# clock-matrix.net
KiCad netlist of a schematic drawn in EAGLE
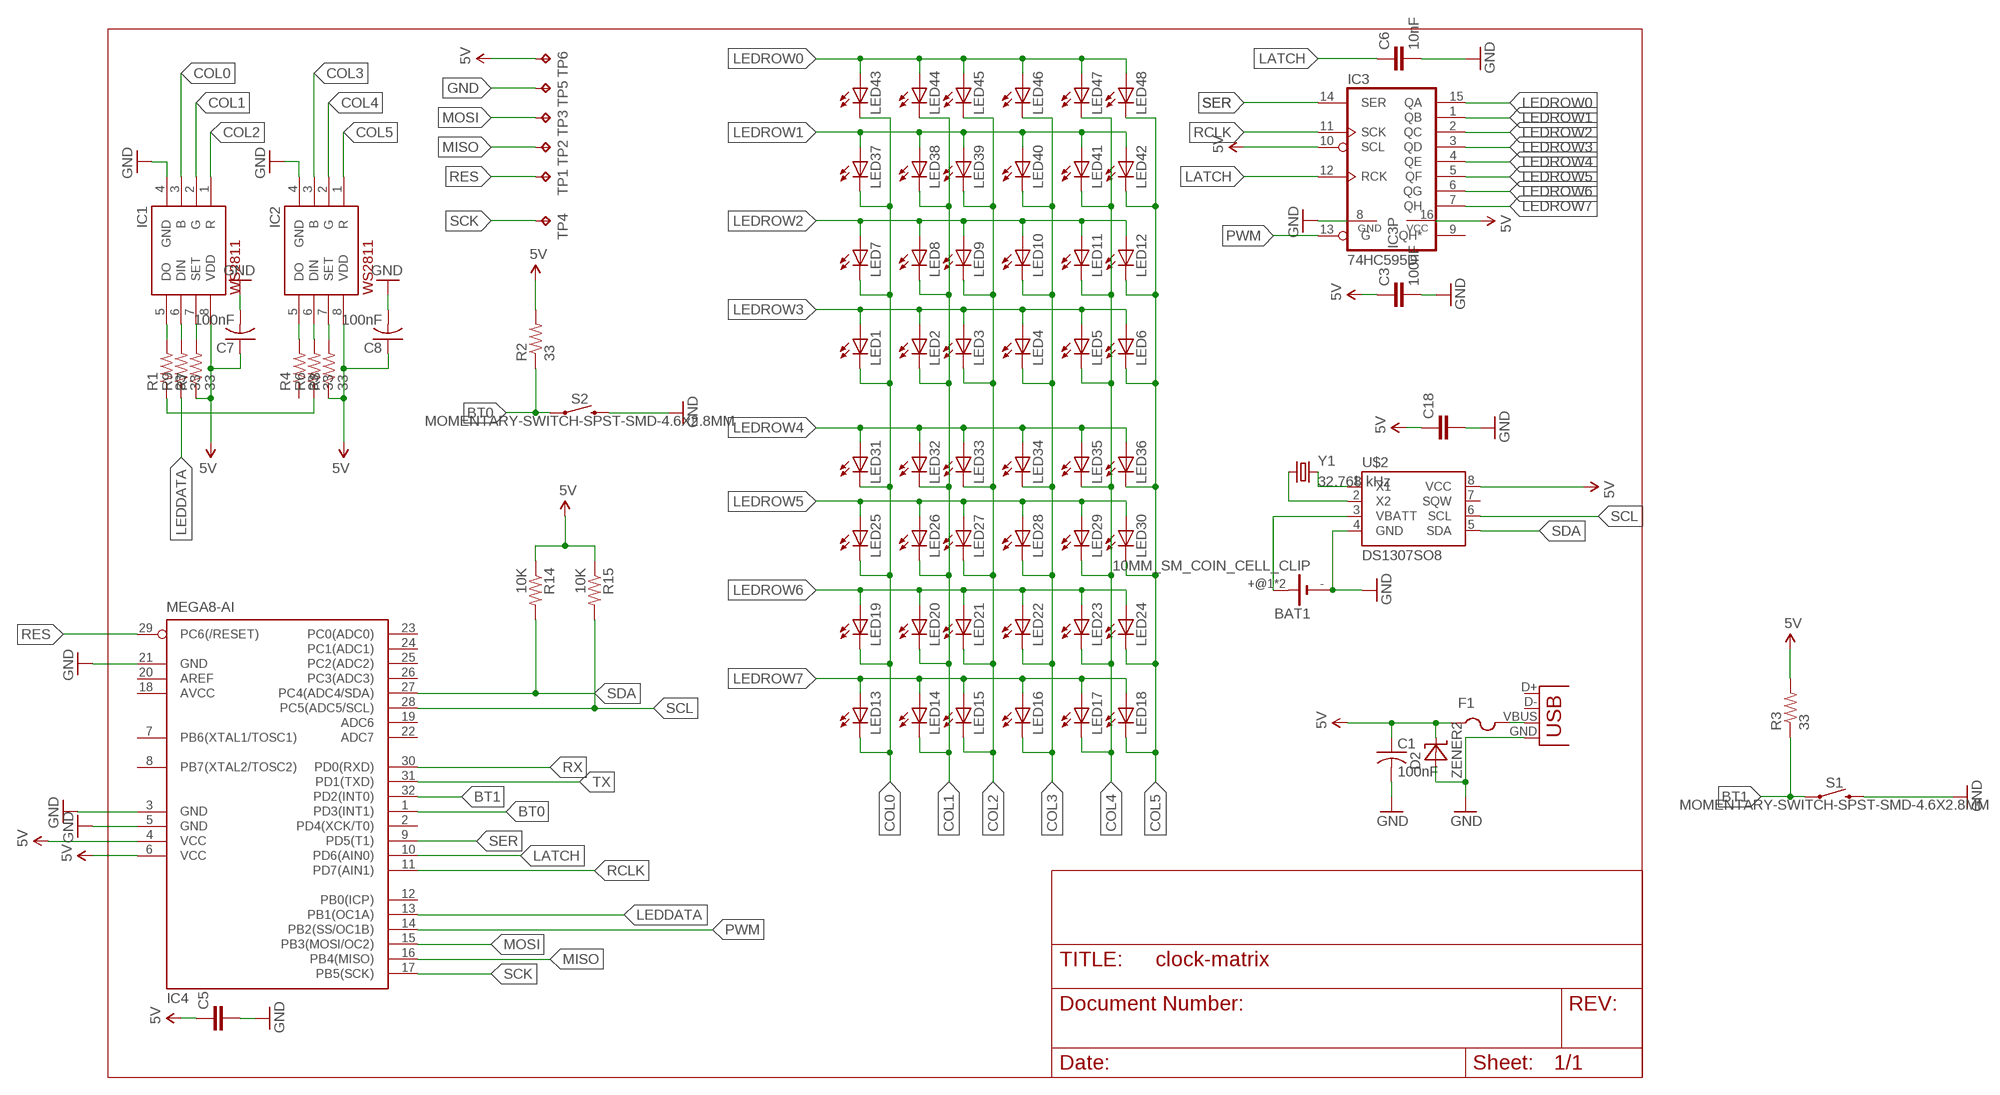
[diagram p0: schematic, sheet 1]

(export (version "E")
  (design (tool "Eeschema 10.0.6"))
  (components
    (comp (ref "BAT1")
      (value "10MM_SM_COIN_CELL_CLIP")
      (footprint "eagle-import:10MM_SM_COIN_CELL_CLIP")
      (libsource (lib "eagle-import") (part "10MM_SM_COIN_CELL_CLIP"))
    )
    (comp (ref "C1")
      (value "100nF")
      (footprint "eagle-import:C0603")
      (libsource (lib "eagle-import") (part "C-USC0603"))
    )
    (comp (ref "C3")
      (value "100nF")
      (footprint "eagle-import:C0603")
      (libsource (lib "eagle-import") (part "C-EUC0603"))
    )
    (comp (ref "C5")
      (value "C-EUC0603")
      (footprint "eagle-import:C0603")
      (libsource (lib "eagle-import") (part "C-EUC0603"))
    )
    (comp (ref "C6")
      (value "10nF")
      (footprint "eagle-import:C0603")
      (libsource (lib "eagle-import") (part "C-EUC0603"))
    )
    (comp (ref "C7")
      (value "100nF")
      (footprint "eagle-import:C0603")
      (libsource (lib "eagle-import") (part "C-USC0603"))
    )
    (comp (ref "C8")
      (value "100nF")
      (footprint "eagle-import:C0603")
      (libsource (lib "eagle-import") (part "C-USC0603"))
    )
    (comp (ref "C18")
      (value "C-EUC0603")
      (footprint "eagle-import:C0603")
      (libsource (lib "eagle-import") (part "C-EUC0603"))
    )
    (comp (ref "D2")
      (value "ZENER2")
      (footprint "eagle-import:SOD123")
      (libsource (lib "eagle-import") (part "ZENER2"))
    )
    (comp (ref "F1")
      (value "PTCFUSE-1206")
      (footprint "eagle-import:R1206")
      (libsource (lib "eagle-import") (part "PTCFUSE-1206"))
    )
    (comp (ref "IC1")
      (value "WS2811-SOP8")
      (footprint "eagle-import:SO08-SKINNYPADS")
      (libsource (lib "eagle-import") (part "WS2811-SOP8"))
    )
    (comp (ref "IC2")
      (value "WS2811-SOP8")
      (footprint "eagle-import:SO08-SKINNYPADS")
      (libsource (lib "eagle-import") (part "WS2811-SOP8"))
    )
    (comp (ref "IC3")
      (value "74HC595D")
      (footprint "eagle-import:SO16")
      (libsource (lib "eagle-import") (part "74595DHC"))
    )
    (comp (ref "IC4")
      (value "MEGA8-AI")
      (footprint "eagle-import:TQFP32-08")
      (fields (field (name "MPN") "ATMEGA8-16AU"))
      (libsource (lib "eagle-import") (part "MEGA8-AI"))
    )
    (comp (ref "LED1")
      (value "LED1206")
      (footprint "eagle-import:LED-1206")
      (libsource (lib "eagle-import") (part "LED1206"))
    )
    (comp (ref "LED2")
      (value "LED1206")
      (footprint "eagle-import:LED-1206")
      (libsource (lib "eagle-import") (part "LED1206"))
    )
    (comp (ref "LED3")
      (value "LED1206")
      (footprint "eagle-import:LED-1206")
      (libsource (lib "eagle-import") (part "LED1206"))
    )
    (comp (ref "LED4")
      (value "LED1206")
      (footprint "eagle-import:LED-1206")
      (libsource (lib "eagle-import") (part "LED1206"))
    )
    (comp (ref "LED5")
      (value "LED1206")
      (footprint "eagle-import:LED-1206")
      (libsource (lib "eagle-import") (part "LED1206"))
    )
    (comp (ref "LED6")
      (value "LED1206")
      (footprint "eagle-import:LED-1206")
      (libsource (lib "eagle-import") (part "LED1206"))
    )
    (comp (ref "LED7")
      (value "LED1206")
      (footprint "eagle-import:LED-1206")
      (libsource (lib "eagle-import") (part "LED1206"))
    )
    (comp (ref "LED8")
      (value "LED1206")
      (footprint "eagle-import:LED-1206")
      (libsource (lib "eagle-import") (part "LED1206"))
    )
    (comp (ref "LED9")
      (value "LED1206")
      (footprint "eagle-import:LED-1206")
      (libsource (lib "eagle-import") (part "LED1206"))
    )
    (comp (ref "LED10")
      (value "LED1206")
      (footprint "eagle-import:LED-1206")
      (libsource (lib "eagle-import") (part "LED1206"))
    )
    (comp (ref "LED11")
      (value "LED1206")
      (footprint "eagle-import:LED-1206")
      (libsource (lib "eagle-import") (part "LED1206"))
    )
    (comp (ref "LED12")
      (value "LED1206")
      (footprint "eagle-import:LED-1206")
      (libsource (lib "eagle-import") (part "LED1206"))
    )
    (comp (ref "LED13")
      (value "LED1206")
      (footprint "eagle-import:LED-1206")
      (libsource (lib "eagle-import") (part "LED1206"))
    )
    (comp (ref "LED14")
      (value "LED1206")
      (footprint "eagle-import:LED-1206")
      (libsource (lib "eagle-import") (part "LED1206"))
    )
    (comp (ref "LED15")
      (value "LED1206")
      (footprint "eagle-import:LED-1206")
      (libsource (lib "eagle-import") (part "LED1206"))
    )
    (comp (ref "LED16")
      (value "LED1206")
      (footprint "eagle-import:LED-1206")
      (libsource (lib "eagle-import") (part "LED1206"))
    )
    (comp (ref "LED17")
      (value "LED1206")
      (footprint "eagle-import:LED-1206")
      (libsource (lib "eagle-import") (part "LED1206"))
    )
    (comp (ref "LED18")
      (value "LED1206")
      (footprint "eagle-import:LED-1206")
      (libsource (lib "eagle-import") (part "LED1206"))
    )
    (comp (ref "LED19")
      (value "LED1206")
      (footprint "eagle-import:LED-1206")
      (libsource (lib "eagle-import") (part "LED1206"))
    )
    (comp (ref "LED20")
      (value "LED1206")
      (footprint "eagle-import:LED-1206")
      (libsource (lib "eagle-import") (part "LED1206"))
    )
    (comp (ref "LED21")
      (value "LED1206")
      (footprint "eagle-import:LED-1206")
      (libsource (lib "eagle-import") (part "LED1206"))
    )
    (comp (ref "LED22")
      (value "LED1206")
      (footprint "eagle-import:LED-1206")
      (libsource (lib "eagle-import") (part "LED1206"))
    )
    (comp (ref "LED23")
      (value "LED1206")
      (footprint "eagle-import:LED-1206")
      (libsource (lib "eagle-import") (part "LED1206"))
    )
    (comp (ref "LED24")
      (value "LED1206")
      (footprint "eagle-import:LED-1206")
      (libsource (lib "eagle-import") (part "LED1206"))
    )
    (comp (ref "LED25")
      (value "LED1206")
      (footprint "eagle-import:LED-1206")
      (libsource (lib "eagle-import") (part "LED1206"))
    )
    (comp (ref "LED26")
      (value "LED1206")
      (footprint "eagle-import:LED-1206")
      (libsource (lib "eagle-import") (part "LED1206"))
    )
    (comp (ref "LED27")
      (value "LED1206")
      (footprint "eagle-import:LED-1206")
      (libsource (lib "eagle-import") (part "LED1206"))
    )
    (comp (ref "LED28")
      (value "LED1206")
      (footprint "eagle-import:LED-1206")
      (libsource (lib "eagle-import") (part "LED1206"))
    )
    (comp (ref "LED29")
      (value "LED1206")
      (footprint "eagle-import:LED-1206")
      (libsource (lib "eagle-import") (part "LED1206"))
    )
    (comp (ref "LED30")
      (value "LED1206")
      (footprint "eagle-import:LED-1206")
      (libsource (lib "eagle-import") (part "LED1206"))
    )
    (comp (ref "LED31")
      (value "LED1206")
      (footprint "eagle-import:LED-1206")
      (libsource (lib "eagle-import") (part "LED1206"))
    )
    (comp (ref "LED32")
      (value "LED1206")
      (footprint "eagle-import:LED-1206")
      (libsource (lib "eagle-import") (part "LED1206"))
    )
    (comp (ref "LED33")
      (value "LED1206")
      (footprint "eagle-import:LED-1206")
      (libsource (lib "eagle-import") (part "LED1206"))
    )
    (comp (ref "LED34")
      (value "LED1206")
      (footprint "eagle-import:LED-1206")
      (libsource (lib "eagle-import") (part "LED1206"))
    )
    (comp (ref "LED35")
      (value "LED1206")
      (footprint "eagle-import:LED-1206")
      (libsource (lib "eagle-import") (part "LED1206"))
    )
    (comp (ref "LED36")
      (value "LED1206")
      (footprint "eagle-import:LED-1206")
      (libsource (lib "eagle-import") (part "LED1206"))
    )
    (comp (ref "LED37")
      (value "LED1206")
      (footprint "eagle-import:LED-1206")
      (libsource (lib "eagle-import") (part "LED1206"))
    )
    (comp (ref "LED38")
      (value "LED1206")
      (footprint "eagle-import:LED-1206")
      (libsource (lib "eagle-import") (part "LED1206"))
    )
    (comp (ref "LED39")
      (value "LED1206")
      (footprint "eagle-import:LED-1206")
      (libsource (lib "eagle-import") (part "LED1206"))
    )
    (comp (ref "LED40")
      (value "LED1206")
      (footprint "eagle-import:LED-1206")
      (libsource (lib "eagle-import") (part "LED1206"))
    )
    (comp (ref "LED41")
      (value "LED1206")
      (footprint "eagle-import:LED-1206")
      (libsource (lib "eagle-import") (part "LED1206"))
    )
    (comp (ref "LED42")
      (value "LED1206")
      (footprint "eagle-import:LED-1206")
      (libsource (lib "eagle-import") (part "LED1206"))
    )
    (comp (ref "LED43")
      (value "LED1206")
      (footprint "eagle-import:LED-1206")
      (libsource (lib "eagle-import") (part "LED1206"))
    )
    (comp (ref "LED44")
      (value "LED1206")
      (footprint "eagle-import:LED-1206")
      (libsource (lib "eagle-import") (part "LED1206"))
    )
    (comp (ref "LED45")
      (value "LED1206")
      (footprint "eagle-import:LED-1206")
      (libsource (lib "eagle-import") (part "LED1206"))
    )
    (comp (ref "LED46")
      (value "LED1206")
      (footprint "eagle-import:LED-1206")
      (libsource (lib "eagle-import") (part "LED1206"))
    )
    (comp (ref "LED47")
      (value "LED1206")
      (footprint "eagle-import:LED-1206")
      (libsource (lib "eagle-import") (part "LED1206"))
    )
    (comp (ref "LED48")
      (value "LED1206")
      (footprint "eagle-import:LED-1206")
      (libsource (lib "eagle-import") (part "LED1206"))
    )
    (comp (ref "R1")
      (value "33")
      (footprint "eagle-import:R0603")
      (libsource (lib "eagle-import") (part "R-US_R0603"))
    )
    (comp (ref "R2")
      (value "33")
      (footprint "eagle-import:R0603")
      (libsource (lib "eagle-import") (part "R-US_R0603"))
    )
    (comp (ref "R3")
      (value "33")
      (footprint "eagle-import:R0603")
      (libsource (lib "eagle-import") (part "R-US_R0603"))
    )
    (comp (ref "R4")
      (value "33")
      (footprint "eagle-import:R0603")
      (libsource (lib "eagle-import") (part "R-US_R0603"))
    )
    (comp (ref "R6")
      (value "33")
      (footprint "eagle-import:R0603")
      (libsource (lib "eagle-import") (part "R-US_R0603"))
    )
    (comp (ref "R7")
      (value "33")
      (footprint "eagle-import:R0603")
      (libsource (lib "eagle-import") (part "R-US_R0603"))
    )
    (comp (ref "R8")
      (value "33")
      (footprint "eagle-import:R0603")
      (libsource (lib "eagle-import") (part "R-US_R0603"))
    )
    (comp (ref "R9")
      (value "33")
      (footprint "eagle-import:R0603")
      (libsource (lib "eagle-import") (part "R-US_R0603"))
    )
    (comp (ref "R14")
      (value "10K")
      (footprint "eagle-import:R0603")
      (libsource (lib "eagle-import") (part "rcl_R-US_R0603"))
    )
    (comp (ref "R15")
      (value "10K")
      (footprint "eagle-import:R0603")
      (libsource (lib "eagle-import") (part "rcl_R-US_R0603"))
    )
    (comp (ref "S1")
      (value "MOMENTARY-SWITCH-SPST-SMD-4.6X2.8MM")
      (footprint "eagle-import:TACTILE_SWITCH_SMD_4.6X2.8MM")
      (libsource (lib "eagle-import") (part "MOMENTARY-SWITCH-SPST-SMD-4.6X2.8MM"))
    )
    (comp (ref "S2")
      (value "MOMENTARY-SWITCH-SPST-SMD-4.6X2.8MM")
      (footprint "eagle-import:TACTILE_SWITCH_SMD_4.6X2.8MM")
      (libsource (lib "eagle-import") (part "MOMENTARY-SWITCH-SPST-SMD-4.6X2.8MM"))
    )
    (comp (ref "TP1")
      (value "TPTP10R")
      (footprint "eagle-import:TP10R")
      (libsource (lib "eagle-import") (part "TPTP10R"))
    )
    (comp (ref "TP2")
      (value "TPTP10R")
      (footprint "eagle-import:TP10R")
      (libsource (lib "eagle-import") (part "TPTP10R"))
    )
    (comp (ref "TP3")
      (value "TPTP10R")
      (footprint "eagle-import:TP10R")
      (libsource (lib "eagle-import") (part "TPTP10R"))
    )
    (comp (ref "TP4")
      (value "TPTP10R")
      (footprint "eagle-import:TP10R")
      (libsource (lib "eagle-import") (part "TPTP10R"))
    )
    (comp (ref "TP5")
      (value "TPTP10R")
      (footprint "eagle-import:TP10R")
      (libsource (lib "eagle-import") (part "TPTP10R"))
    )
    (comp (ref "TP6")
      (value "TPTP10R")
      (footprint "eagle-import:TP10R")
      (libsource (lib "eagle-import") (part "TPTP10R"))
    )
    (comp (ref "U$2")
      (value "DS1307SO8")
      (footprint "eagle-import:SO08")
      (libsource (lib "eagle-import") (part "DS1307SO8"))
    )
    (comp (ref "X2")
      (value "USB-MICROB")
      (footprint "eagle-import:USB-MICROB")
      (libsource (lib "eagle-import") (part "USB-MICROB"))
    )
    (comp (ref "Y1")
      (value "32.768 kHz")
      (footprint "eagle-import:TC26H")
      (libsource (lib "eagle-import") (part "CRYSTALTC26H"))
    )
  )
  (nets
    (net (code "1") (name "/AVCC") (class "Default")
      (node (ref "IC4") (pin "18") (pinfunction "AVCC_18") (pintype "power_in"))
    )
    (net (code "2") (name "5V") (class "Default")
      (node (ref "C1") (pin "1") (pinfunction "1_1") (pintype "passive"))
      (node (ref "C18") (pin "1") (pinfunction "1_1") (pintype "passive"))
      (node (ref "C3") (pin "1") (pinfunction "1_1") (pintype "passive"))
      (node (ref "C5") (pin "1") (pinfunction "1_1") (pintype "passive"))
      (node (ref "C7") (pin "1") (pinfunction "1_1") (pintype "passive"))
      (node (ref "C8") (pin "1") (pinfunction "1_1") (pintype "passive"))
      (node (ref "D2") (pin "C") (pinfunction "C_C") (pintype "passive"))
      (node (ref "F1") (pin "1") (pinfunction "1_1") (pintype "passive"))
      (node (ref "IC1") (pin "8") (pinfunction "VDD_8") (pintype "power_in"))
      (node (ref "IC2") (pin "8") (pinfunction "VDD_8") (pintype "power_in"))
      (node (ref "IC3") (pin "10") (pinfunction "SCL_10") (pintype "input"))
      (node (ref "IC3") (pin "16") (pinfunction "VCC_16") (pintype "power_in"))
      (node (ref "IC4") (pin "4") (pinfunction "VCC_4") (pintype "power_in"))
      (node (ref "IC4") (pin "6") (pinfunction "VCC_6") (pintype "power_in"))
      (node (ref "R14") (pin "1") (pinfunction "1_1") (pintype "passive"))
      (node (ref "R15") (pin "1") (pinfunction "1_1") (pintype "passive"))
      (node (ref "R2") (pin "2") (pinfunction "2_2") (pintype "passive"))
      (node (ref "R3") (pin "2") (pinfunction "2_2") (pintype "passive"))
      (node (ref "R7") (pin "1") (pinfunction "1_1") (pintype "passive"))
      (node (ref "R8") (pin "1") (pinfunction "1_1") (pintype "passive"))
      (node (ref "TP6") (pin "TP") (pinfunction "TP_TP") (pintype "input"))
      (node (ref "U$2") (pin "8") (pinfunction "VCC_8") (pintype "bidirectional"))
    )
    (net (code "3") (name "BT0") (class "Default")
      (node (ref "IC4") (pin "1") (pinfunction "PD3(INT1)_1") (pintype "bidirectional"))
      (node (ref "R2") (pin "1") (pinfunction "1_1") (pintype "passive"))
      (node (ref "S2") (pin "1") (pinfunction "1_1") (pintype "passive"))
      (node (ref "S2") (pin "2") (pinfunction "1_2") (pintype "passive"))
    )
    (net (code "4") (name "BT1") (class "Default")
      (node (ref "IC4") (pin "32") (pinfunction "PD2(INT0)_32") (pintype "bidirectional"))
      (node (ref "R3") (pin "1") (pinfunction "1_1") (pintype "passive"))
      (node (ref "S1") (pin "1") (pinfunction "1_1") (pintype "passive"))
      (node (ref "S1") (pin "2") (pinfunction "1_2") (pintype "passive"))
    )
    (net (code "5") (name "COL0") (class "Default")
      (node (ref "IC1") (pin "3") (pinfunction "B_3") (pintype "open_collector"))
      (node (ref "LED1") (pin "C") (pinfunction "C_C") (pintype "passive"))
      (node (ref "LED13") (pin "C") (pinfunction "C_C") (pintype "passive"))
      (node (ref "LED19") (pin "C") (pinfunction "C_C") (pintype "passive"))
      (node (ref "LED25") (pin "C") (pinfunction "C_C") (pintype "passive"))
      (node (ref "LED31") (pin "C") (pinfunction "C_C") (pintype "passive"))
      (node (ref "LED37") (pin "C") (pinfunction "C_C") (pintype "passive"))
      (node (ref "LED43") (pin "C") (pinfunction "C_C") (pintype "passive"))
      (node (ref "LED7") (pin "C") (pinfunction "C_C") (pintype "passive"))
    )
    (net (code "6") (name "COL1") (class "Default")
      (node (ref "IC1") (pin "2") (pinfunction "G_2") (pintype "open_collector"))
      (node (ref "LED14") (pin "C") (pinfunction "C_C") (pintype "passive"))
      (node (ref "LED2") (pin "C") (pinfunction "C_C") (pintype "passive"))
      (node (ref "LED20") (pin "C") (pinfunction "C_C") (pintype "passive"))
      (node (ref "LED26") (pin "C") (pinfunction "C_C") (pintype "passive"))
      (node (ref "LED32") (pin "C") (pinfunction "C_C") (pintype "passive"))
      (node (ref "LED38") (pin "C") (pinfunction "C_C") (pintype "passive"))
      (node (ref "LED44") (pin "C") (pinfunction "C_C") (pintype "passive"))
      (node (ref "LED8") (pin "C") (pinfunction "C_C") (pintype "passive"))
    )
    (net (code "7") (name "COL2") (class "Default")
      (node (ref "IC1") (pin "1") (pinfunction "R_1") (pintype "open_collector"))
      (node (ref "LED15") (pin "C") (pinfunction "C_C") (pintype "passive"))
      (node (ref "LED21") (pin "C") (pinfunction "C_C") (pintype "passive"))
      (node (ref "LED27") (pin "C") (pinfunction "C_C") (pintype "passive"))
      (node (ref "LED3") (pin "C") (pinfunction "C_C") (pintype "passive"))
      (node (ref "LED33") (pin "C") (pinfunction "C_C") (pintype "passive"))
      (node (ref "LED39") (pin "C") (pinfunction "C_C") (pintype "passive"))
      (node (ref "LED45") (pin "C") (pinfunction "C_C") (pintype "passive"))
      (node (ref "LED9") (pin "C") (pinfunction "C_C") (pintype "passive"))
    )
    (net (code "8") (name "COL3") (class "Default")
      (node (ref "IC2") (pin "3") (pinfunction "B_3") (pintype "open_collector"))
      (node (ref "LED10") (pin "C") (pinfunction "C_C") (pintype "passive"))
      (node (ref "LED16") (pin "C") (pinfunction "C_C") (pintype "passive"))
      (node (ref "LED22") (pin "C") (pinfunction "C_C") (pintype "passive"))
      (node (ref "LED28") (pin "C") (pinfunction "C_C") (pintype "passive"))
      (node (ref "LED34") (pin "C") (pinfunction "C_C") (pintype "passive"))
      (node (ref "LED4") (pin "C") (pinfunction "C_C") (pintype "passive"))
      (node (ref "LED40") (pin "C") (pinfunction "C_C") (pintype "passive"))
      (node (ref "LED46") (pin "C") (pinfunction "C_C") (pintype "passive"))
    )
    (net (code "9") (name "COL4") (class "Default")
      (node (ref "IC2") (pin "2") (pinfunction "G_2") (pintype "open_collector"))
      (node (ref "LED11") (pin "C") (pinfunction "C_C") (pintype "passive"))
      (node (ref "LED17") (pin "C") (pinfunction "C_C") (pintype "passive"))
      (node (ref "LED23") (pin "C") (pinfunction "C_C") (pintype "passive"))
      (node (ref "LED29") (pin "C") (pinfunction "C_C") (pintype "passive"))
      (node (ref "LED35") (pin "C") (pinfunction "C_C") (pintype "passive"))
      (node (ref "LED41") (pin "C") (pinfunction "C_C") (pintype "passive"))
      (node (ref "LED47") (pin "C") (pinfunction "C_C") (pintype "passive"))
      (node (ref "LED5") (pin "C") (pinfunction "C_C") (pintype "passive"))
    )
    (net (code "10") (name "COL5") (class "Default")
      (node (ref "IC2") (pin "1") (pinfunction "R_1") (pintype "open_collector"))
      (node (ref "LED12") (pin "C") (pinfunction "C_C") (pintype "passive"))
      (node (ref "LED18") (pin "C") (pinfunction "C_C") (pintype "passive"))
      (node (ref "LED24") (pin "C") (pinfunction "C_C") (pintype "passive"))
      (node (ref "LED30") (pin "C") (pinfunction "C_C") (pintype "passive"))
      (node (ref "LED36") (pin "C") (pinfunction "C_C") (pintype "passive"))
      (node (ref "LED42") (pin "C") (pinfunction "C_C") (pintype "passive"))
      (node (ref "LED48") (pin "C") (pinfunction "C_C") (pintype "passive"))
      (node (ref "LED6") (pin "C") (pinfunction "C_C") (pintype "passive"))
    )
    (net (code "11") (name "GND") (class "Default")
      (node (ref "BAT1") (pin "-") (pinfunction "-_-") (pintype "passive"))
      (node (ref "C1") (pin "2") (pinfunction "2_2") (pintype "passive"))
      (node (ref "C18") (pin "2") (pinfunction "2_2") (pintype "passive"))
      (node (ref "C3") (pin "2") (pinfunction "2_2") (pintype "passive"))
      (node (ref "C5") (pin "2") (pinfunction "2_2") (pintype "passive"))
      (node (ref "C6") (pin "2") (pinfunction "2_2") (pintype "passive"))
      (node (ref "C7") (pin "2") (pinfunction "2_2") (pintype "passive"))
      (node (ref "C8") (pin "2") (pinfunction "2_2") (pintype "passive"))
      (node (ref "D2") (pin "A") (pinfunction "A_A") (pintype "passive"))
      (node (ref "IC1") (pin "4") (pinfunction "GND_4") (pintype "power_in"))
      (node (ref "IC2") (pin "4") (pinfunction "GND_4") (pintype "power_in"))
      (node (ref "IC3") (pin "8") (pinfunction "GND_8") (pintype "power_in"))
      (node (ref "IC4") (pin "21") (pinfunction "GND_21") (pintype "power_in"))
      (node (ref "IC4") (pin "3") (pinfunction "GND_3") (pintype "power_in"))
      (node (ref "IC4") (pin "5") (pinfunction "GND_5") (pintype "power_in"))
      (node (ref "S1") (pin "3") (pinfunction "2_3") (pintype "passive"))
      (node (ref "S1") (pin "4") (pinfunction "2_4") (pintype "passive"))
      (node (ref "S2") (pin "3") (pinfunction "2_3") (pintype "passive"))
      (node (ref "S2") (pin "4") (pinfunction "2_4") (pintype "passive"))
      (node (ref "TP5") (pin "TP") (pinfunction "TP_TP") (pintype "input"))
      (node (ref "U$2") (pin "4") (pinfunction "GND_4") (pintype "bidirectional"))
      (node (ref "X2") (pin "GND") (pinfunction "GND_GND") (pintype "bidirectional"))
    )
    (net (code "12") (name "LATCH") (class "Default")
      (node (ref "C6") (pin "1") (pinfunction "1_1") (pintype "passive"))
      (node (ref "IC3") (pin "12") (pinfunction "RCK_12") (pintype "input"))
      (node (ref "IC4") (pin "10") (pinfunction "PD6(AIN0)_10") (pintype "bidirectional"))
    )
    (net (code "13") (name "LEDDATA") (class "Default")
      (node (ref "IC4") (pin "13") (pinfunction "PB1(OC1A)_13") (pintype "bidirectional"))
      (node (ref "R9") (pin "1") (pinfunction "1_1") (pintype "passive"))
    )
    (net (code "14") (name "LEDROW0") (class "Default")
      (node (ref "IC3") (pin "15") (pinfunction "QA_15") (pintype "tri_state"))
      (node (ref "LED43") (pin "A") (pinfunction "A_A") (pintype "passive"))
      (node (ref "LED44") (pin "A") (pinfunction "A_A") (pintype "passive"))
      (node (ref "LED45") (pin "A") (pinfunction "A_A") (pintype "passive"))
      (node (ref "LED46") (pin "A") (pinfunction "A_A") (pintype "passive"))
      (node (ref "LED47") (pin "A") (pinfunction "A_A") (pintype "passive"))
      (node (ref "LED48") (pin "A") (pinfunction "A_A") (pintype "passive"))
    )
    (net (code "15") (name "LEDROW1") (class "Default")
      (node (ref "IC3") (pin "1") (pinfunction "QB_1") (pintype "tri_state"))
      (node (ref "LED37") (pin "A") (pinfunction "A_A") (pintype "passive"))
      (node (ref "LED38") (pin "A") (pinfunction "A_A") (pintype "passive"))
      (node (ref "LED39") (pin "A") (pinfunction "A_A") (pintype "passive"))
      (node (ref "LED40") (pin "A") (pinfunction "A_A") (pintype "passive"))
      (node (ref "LED41") (pin "A") (pinfunction "A_A") (pintype "passive"))
      (node (ref "LED42") (pin "A") (pinfunction "A_A") (pintype "passive"))
    )
    (net (code "16") (name "LEDROW2") (class "Default")
      (node (ref "IC3") (pin "2") (pinfunction "QC_2") (pintype "tri_state"))
      (node (ref "LED10") (pin "A") (pinfunction "A_A") (pintype "passive"))
      (node (ref "LED11") (pin "A") (pinfunction "A_A") (pintype "passive"))
      (node (ref "LED12") (pin "A") (pinfunction "A_A") (pintype "passive"))
      (node (ref "LED7") (pin "A") (pinfunction "A_A") (pintype "passive"))
      (node (ref "LED8") (pin "A") (pinfunction "A_A") (pintype "passive"))
      (node (ref "LED9") (pin "A") (pinfunction "A_A") (pintype "passive"))
    )
    (net (code "17") (name "LEDROW3") (class "Default")
      (node (ref "IC3") (pin "3") (pinfunction "QD_3") (pintype "tri_state"))
      (node (ref "LED1") (pin "A") (pinfunction "A_A") (pintype "passive"))
      (node (ref "LED2") (pin "A") (pinfunction "A_A") (pintype "passive"))
      (node (ref "LED3") (pin "A") (pinfunction "A_A") (pintype "passive"))
      (node (ref "LED4") (pin "A") (pinfunction "A_A") (pintype "passive"))
      (node (ref "LED5") (pin "A") (pinfunction "A_A") (pintype "passive"))
      (node (ref "LED6") (pin "A") (pinfunction "A_A") (pintype "passive"))
    )
    (net (code "18") (name "LEDROW4") (class "Default")
      (node (ref "IC3") (pin "4") (pinfunction "QE_4") (pintype "tri_state"))
      (node (ref "LED31") (pin "A") (pinfunction "A_A") (pintype "passive"))
      (node (ref "LED32") (pin "A") (pinfunction "A_A") (pintype "passive"))
      (node (ref "LED33") (pin "A") (pinfunction "A_A") (pintype "passive"))
      (node (ref "LED34") (pin "A") (pinfunction "A_A") (pintype "passive"))
      (node (ref "LED35") (pin "A") (pinfunction "A_A") (pintype "passive"))
      (node (ref "LED36") (pin "A") (pinfunction "A_A") (pintype "passive"))
    )
    (net (code "19") (name "LEDROW5") (class "Default")
      (node (ref "IC3") (pin "5") (pinfunction "QF_5") (pintype "tri_state"))
      (node (ref "LED25") (pin "A") (pinfunction "A_A") (pintype "passive"))
      (node (ref "LED26") (pin "A") (pinfunction "A_A") (pintype "passive"))
      (node (ref "LED27") (pin "A") (pinfunction "A_A") (pintype "passive"))
      (node (ref "LED28") (pin "A") (pinfunction "A_A") (pintype "passive"))
      (node (ref "LED29") (pin "A") (pinfunction "A_A") (pintype "passive"))
      (node (ref "LED30") (pin "A") (pinfunction "A_A") (pintype "passive"))
    )
    (net (code "20") (name "LEDROW6") (class "Default")
      (node (ref "IC3") (pin "6") (pinfunction "QG_6") (pintype "tri_state"))
      (node (ref "LED19") (pin "A") (pinfunction "A_A") (pintype "passive"))
      (node (ref "LED20") (pin "A") (pinfunction "A_A") (pintype "passive"))
      (node (ref "LED21") (pin "A") (pinfunction "A_A") (pintype "passive"))
      (node (ref "LED22") (pin "A") (pinfunction "A_A") (pintype "passive"))
      (node (ref "LED23") (pin "A") (pinfunction "A_A") (pintype "passive"))
      (node (ref "LED24") (pin "A") (pinfunction "A_A") (pintype "passive"))
    )
    (net (code "21") (name "LEDROW7") (class "Default")
      (node (ref "IC3") (pin "7") (pinfunction "QH_7") (pintype "tri_state"))
      (node (ref "LED13") (pin "A") (pinfunction "A_A") (pintype "passive"))
      (node (ref "LED14") (pin "A") (pinfunction "A_A") (pintype "passive"))
      (node (ref "LED15") (pin "A") (pinfunction "A_A") (pintype "passive"))
      (node (ref "LED16") (pin "A") (pinfunction "A_A") (pintype "passive"))
      (node (ref "LED17") (pin "A") (pinfunction "A_A") (pintype "passive"))
      (node (ref "LED18") (pin "A") (pinfunction "A_A") (pintype "passive"))
    )
    (net (code "22") (name "MISO") (class "Default")
      (node (ref "IC4") (pin "16") (pinfunction "PB4(MISO)_16") (pintype "bidirectional"))
      (node (ref "TP2") (pin "TP") (pinfunction "TP_TP") (pintype "input"))
    )
    (net (code "23") (name "MOSI") (class "Default")
      (node (ref "IC4") (pin "15") (pinfunction "PB3(MOSI/OC2)_15") (pintype "bidirectional"))
      (node (ref "TP3") (pin "TP") (pinfunction "TP_TP") (pintype "input"))
    )
    (net (code "24") (name "Net-(F1-Pad2)") (class "Default")
      (node (ref "F1") (pin "2") (pinfunction "2_2") (pintype "passive"))
      (node (ref "X2") (pin "VBUS") (pinfunction "VBUS_VBUS") (pintype "bidirectional"))
    )
    (net (code "25") (name "Net-(IC1-DIN)") (class "Default")
      (node (ref "IC1") (pin "6") (pinfunction "DIN_6") (pintype "input"))
      (node (ref "R9") (pin "2") (pinfunction "2_2") (pintype "passive"))
    )
    (net (code "26") (name "Net-(IC1-DO)") (class "Default")
      (node (ref "IC1") (pin "5") (pinfunction "DO_5") (pintype "output"))
      (node (ref "R1") (pin "2") (pinfunction "2_2") (pintype "passive"))
    )
    (net (code "27") (name "Net-(IC1-SET)") (class "Default")
      (node (ref "IC1") (pin "7") (pinfunction "SET_7") (pintype "input"))
      (node (ref "R7") (pin "2") (pinfunction "2_2") (pintype "passive"))
    )
    (net (code "28") (name "Net-(IC2-DIN)") (class "Default")
      (node (ref "IC2") (pin "6") (pinfunction "DIN_6") (pintype "input"))
      (node (ref "R6") (pin "2") (pinfunction "2_2") (pintype "passive"))
    )
    (net (code "29") (name "Net-(IC2-DO)") (class "Default")
      (node (ref "IC2") (pin "5") (pinfunction "DO_5") (pintype "output"))
      (node (ref "R4") (pin "2") (pinfunction "2_2") (pintype "passive"))
    )
    (net (code "30") (name "Net-(IC2-SET)") (class "Default")
      (node (ref "IC2") (pin "7") (pinfunction "SET_7") (pintype "input"))
      (node (ref "R8") (pin "2") (pinfunction "2_2") (pintype "passive"))
    )
    (net (code "31") (name "Net-(R1-Pad1)") (class "Default")
      (node (ref "R1") (pin "1") (pinfunction "1_1") (pintype "passive"))
      (node (ref "R6") (pin "1") (pinfunction "1_1") (pintype "passive"))
    )
    (net (code "32") (name "Net-(U$2-VBATT)") (class "Default")
      (node (ref "BAT1") (pin "+@1") (pinfunction "+_+@1") (pintype "passive"))
      (node (ref "BAT1") (pin "+@2") (pinfunction "+_+@2") (pintype "passive"))
      (node (ref "U$2") (pin "3") (pinfunction "VBATT_3") (pintype "bidirectional"))
    )
    (net (code "33") (name "Net-(U$2-X1)") (class "Default")
      (node (ref "U$2") (pin "1") (pinfunction "X1_1") (pintype "bidirectional"))
      (node (ref "Y1") (pin "2") (pinfunction "2_2") (pintype "passive"))
    )
    (net (code "34") (name "Net-(U$2-X2)") (class "Default")
      (node (ref "U$2") (pin "2") (pinfunction "X2_2") (pintype "bidirectional"))
      (node (ref "Y1") (pin "1") (pinfunction "1_1") (pintype "passive"))
    )
    (net (code "35") (name "PWM") (class "Default")
      (node (ref "IC3") (pin "13") (pinfunction "G_13") (pintype "input"))
      (node (ref "IC4") (pin "14") (pinfunction "PB2(SS/OC1B)_14") (pintype "bidirectional"))
    )
    (net (code "36") (name "RCLK") (class "Default")
      (node (ref "IC3") (pin "11") (pinfunction "SCK_11") (pintype "input"))
      (node (ref "IC4") (pin "11") (pinfunction "PD7(AIN1)_11") (pintype "bidirectional"))
    )
    (net (code "37") (name "RES") (class "Default")
      (node (ref "IC4") (pin "29") (pinfunction "PC6(/RESET)_29") (pintype "bidirectional"))
      (node (ref "TP1") (pin "TP") (pinfunction "TP_TP") (pintype "input"))
    )
    (net (code "38") (name "RX") (class "Default")
      (node (ref "IC4") (pin "30") (pinfunction "PD0(RXD)_30") (pintype "bidirectional"))
    )
    (net (code "39") (name "SCK") (class "Default")
      (node (ref "IC4") (pin "17") (pinfunction "PB5(SCK)_17") (pintype "bidirectional"))
      (node (ref "TP4") (pin "TP") (pinfunction "TP_TP") (pintype "input"))
    )
    (net (code "40") (name "SCL") (class "Default")
      (node (ref "IC4") (pin "28") (pinfunction "PC5(ADC5/SCL)_28") (pintype "bidirectional"))
      (node (ref "R15") (pin "2") (pinfunction "2_2") (pintype "passive"))
      (node (ref "U$2") (pin "6") (pinfunction "SCL_6") (pintype "bidirectional"))
    )
    (net (code "41") (name "SDA") (class "Default")
      (node (ref "IC4") (pin "27") (pinfunction "PC4(ADC4/SDA)_27") (pintype "bidirectional"))
      (node (ref "R14") (pin "2") (pinfunction "2_2") (pintype "passive"))
      (node (ref "U$2") (pin "5") (pinfunction "SDA_5") (pintype "bidirectional"))
    )
    (net (code "42") (name "SER") (class "Default")
      (node (ref "IC3") (pin "14") (pinfunction "SER_14") (pintype "input"))
      (node (ref "IC4") (pin "9") (pinfunction "PD5(T1)_9") (pintype "bidirectional"))
    )
    (net (code "43") (name "TX") (class "Default")
      (node (ref "IC4") (pin "31") (pinfunction "PD1(TXD)_31") (pintype "bidirectional"))
    )
    (net (code "44") (name "unconnected-(IC3A-QH*-Pad9)") (class "Default")
      (node (ref "IC3") (pin "9") (pinfunction "QH*_9") (pintype "tri_state"))
    )
    (net (code "45") (name "unconnected-(IC4-ADC6-Pad19)") (class "Default")
      (node (ref "IC4") (pin "19") (pinfunction "ADC6_19") (pintype "bidirectional"))
    )
    (net (code "46") (name "unconnected-(IC4-ADC7-Pad22)") (class "Default")
      (node (ref "IC4") (pin "22") (pinfunction "ADC7_22") (pintype "bidirectional"))
    )
    (net (code "47") (name "unconnected-(IC4-AREF-Pad20)") (class "Default")
      (node (ref "IC4") (pin "20") (pinfunction "AREF_20") (pintype "passive"))
    )
    (net (code "48") (name "unconnected-(IC4-PB0(ICP)-Pad12)") (class "Default")
      (node (ref "IC4") (pin "12") (pinfunction "PB0(ICP)_12") (pintype "bidirectional"))
    )
    (net (code "49") (name "unconnected-(IC4-PB6(XTAL1{slash}TOSC1)-Pad7)") (class "Default")
      (node (ref "IC4") (pin "7") (pinfunction "PB6(XTAL1/TOSC1)_7") (pintype "bidirectional"))
    )
    (net (code "50") (name "unconnected-(IC4-PB7(XTAL2{slash}TOSC2)-Pad8)") (class "Default")
      (node (ref "IC4") (pin "8") (pinfunction "PB7(XTAL2/TOSC2)_8") (pintype "bidirectional"))
    )
    (net (code "51") (name "unconnected-(IC4-PC0(ADC0)-Pad23)") (class "Default")
      (node (ref "IC4") (pin "23") (pinfunction "PC0(ADC0)_23") (pintype "bidirectional"))
    )
    (net (code "52") (name "unconnected-(IC4-PC1(ADC1)-Pad24)") (class "Default")
      (node (ref "IC4") (pin "24") (pinfunction "PC1(ADC1)_24") (pintype "bidirectional"))
    )
    (net (code "53") (name "unconnected-(IC4-PC2(ADC2)-Pad25)") (class "Default")
      (node (ref "IC4") (pin "25") (pinfunction "PC2(ADC2)_25") (pintype "bidirectional"))
    )
    (net (code "54") (name "unconnected-(IC4-PC3(ADC3)-Pad26)") (class "Default")
      (node (ref "IC4") (pin "26") (pinfunction "PC3(ADC3)_26") (pintype "bidirectional"))
    )
    (net (code "55") (name "unconnected-(IC4-PD4(XCK{slash}T0)-Pad2)") (class "Default")
      (node (ref "IC4") (pin "2") (pinfunction "PD4(XCK/T0)_2") (pintype "bidirectional"))
    )
    (net (code "56") (name "unconnected-(R4-Pad1)") (class "Default")
      (node (ref "R4") (pin "1") (pinfunction "1_1") (pintype "passive"))
    )
    (net (code "57") (name "unconnected-(U$2-SQW-Pad7)") (class "Default")
      (node (ref "U$2") (pin "7") (pinfunction "SQW_7") (pintype "bidirectional"))
    )
    (net (code "58") (name "unconnected-(X2-PadD+)") (class "Default")
      (node (ref "X2") (pin "D+") (pinfunction "D+_D+") (pintype "bidirectional"))
    )
    (net (code "59") (name "unconnected-(X2-PadD-)") (class "Default")
      (node (ref "X2") (pin "D-") (pinfunction "D-_D-") (pintype "bidirectional"))
    )
  )
)
